# shield_sporecollector_v4.net
KiCad netlist of a schematic drawn in EAGLE
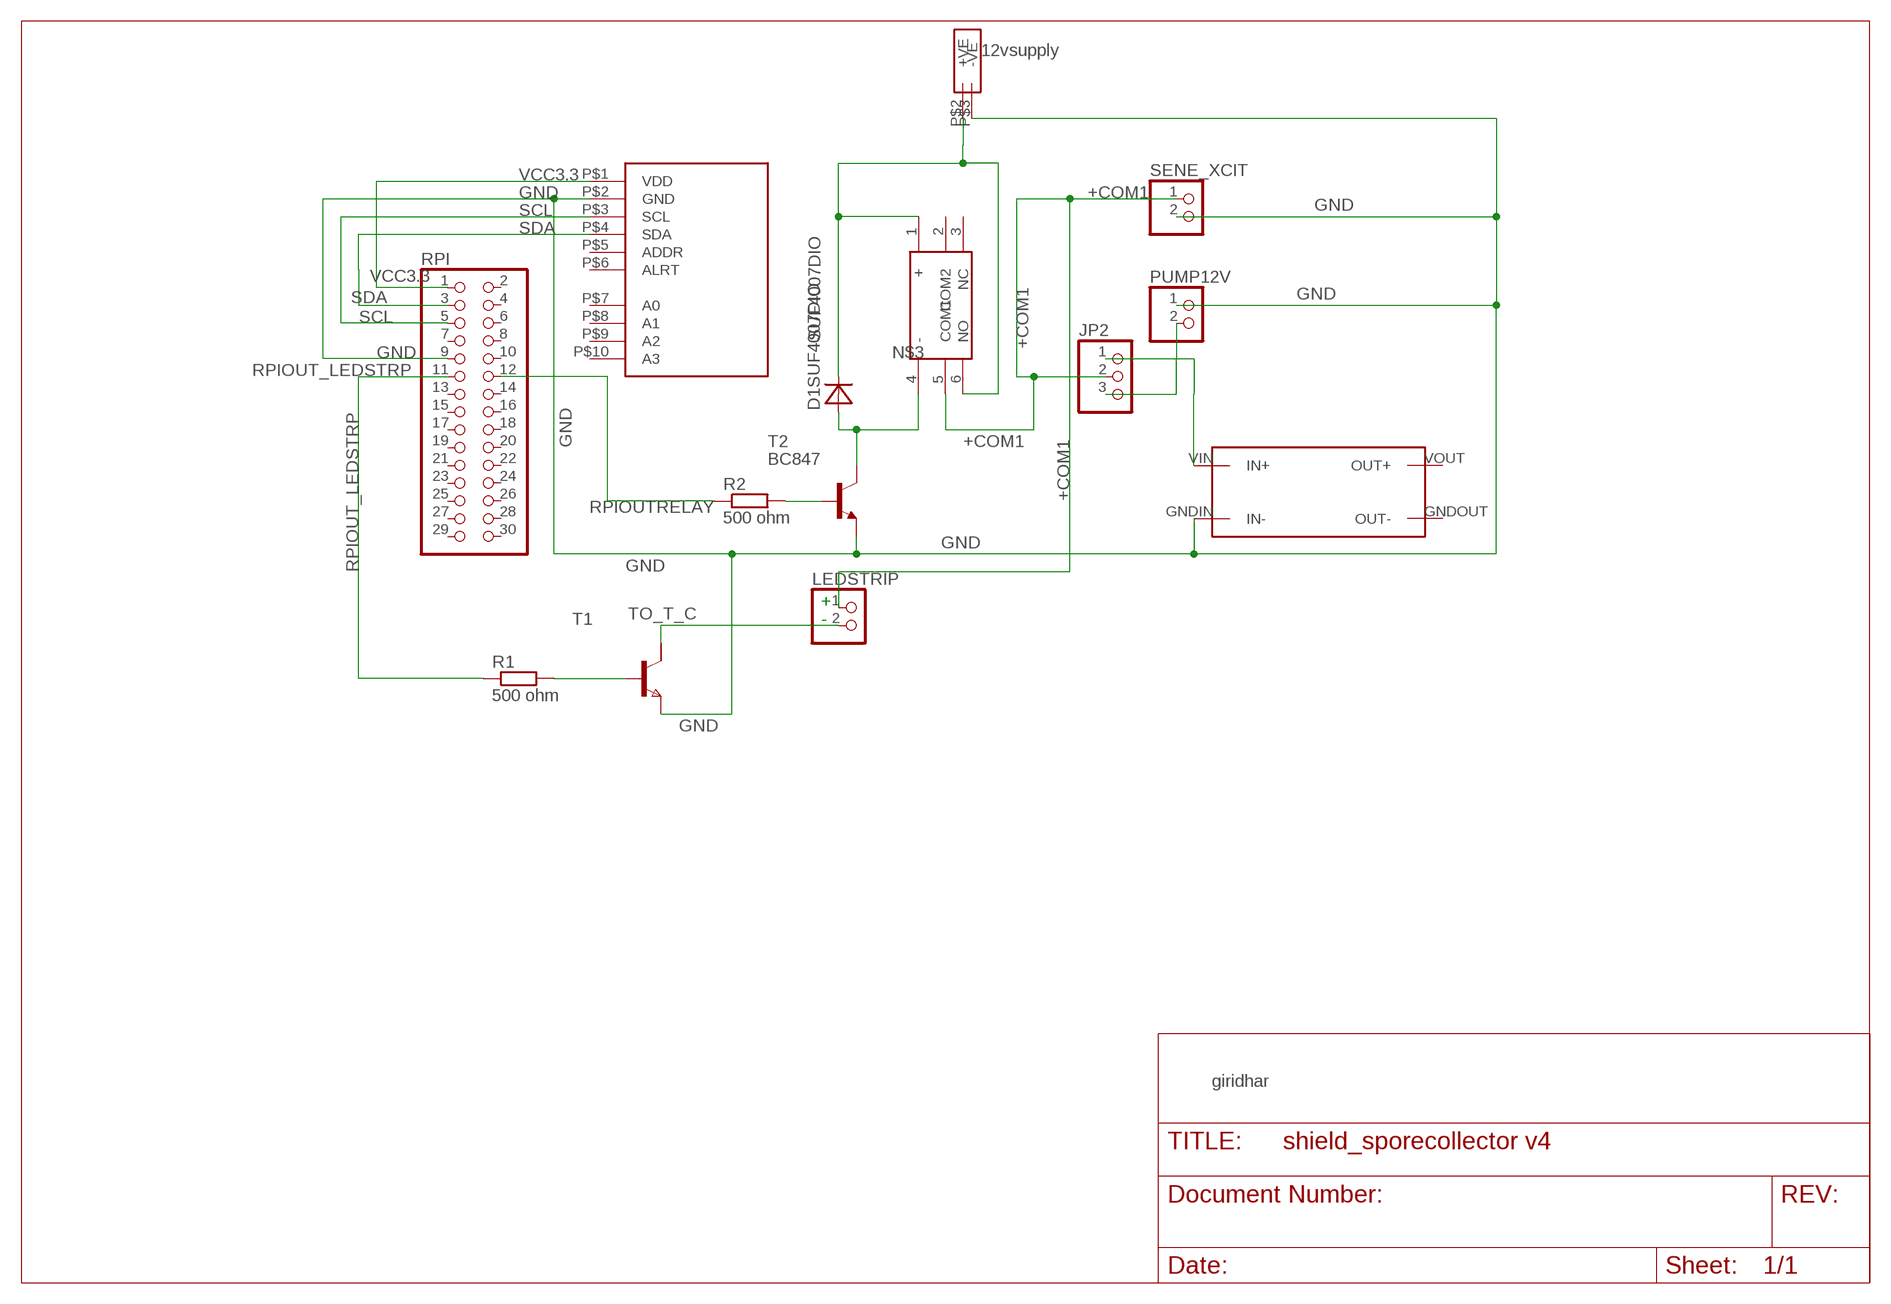
[diagram p0: schematic, sheet 1]

(export (version "E")
  (design (tool "Eeschema 10.0.6"))
  (components
    (comp (ref "BUCHSE12VINPUT")
      (value "BUCHSE9.8X14.6")
      (footprint "eagle-import:BUCHSE9.8X14.6")
      (libsource (lib "eagle-import") (part "BUCHSE9.8X14.6"))
    )
    (comp (ref "D1SUF4007DIO")
      (value "SUF4007DIO")
      (footprint "eagle-import:SUF4007")
      (libsource (lib "eagle-import") (part "SUF4007DIO"))
    )
    (comp (ref "JP2")
      (value "PINHD-1X3")
      (footprint "eagle-import:1X03")
      (libsource (lib "eagle-import") (part "PINHD-1X3"))
    )
    (comp (ref "LEDSTRIP")
      (value "PINHD-1X2")
      (footprint "eagle-import:1X02")
      (libsource (lib "eagle-import") (part "PINHD-1X2"))
    )
    (comp (ref "PUMP12V")
      (value "PINHD-1X2")
      (footprint "eagle-import:1X02")
      (libsource (lib "eagle-import") (part "PINHD-1X2"))
    )
    (comp (ref "R1")
      (value "500 ohm")
      (footprint "eagle-import:R0603")
      (libsource (lib "eagle-import") (part "R-EU_R0603"))
    )
    (comp (ref "R2")
      (value "500 ohm")
      (footprint "eagle-import:R0603")
      (libsource (lib "eagle-import") (part "R-EU_R0603"))
    )
    (comp (ref "RPI")
      (value "PINHD-2X15")
      (footprint "eagle-import:2X15")
      (libsource (lib "eagle-import") (part "PINHD-2X15"))
    )
    (comp (ref "SENE_XCIT")
      (value "PINHD-1X2")
      (footprint "eagle-import:1X02")
      (libsource (lib "eagle-import") (part "PINHD-1X2"))
    )
    (comp (ref "STEPUP12TO24V")
      (value "24VSTEPUPPOLOLUSMDSMD")
      (footprint "eagle-import:STEP-UP24VSMD")
      (libsource (lib "eagle-import") (part "24VSTEPUPPOLOLUSMDSMD"))
    )
    (comp (ref "T1")
      (value "NPNSOT223")
      (footprint "eagle-import:SOT223")
      (libsource (lib "eagle-import") (part "NPNSOT223"))
    )
    (comp (ref "T2")
      (value "BC847")
      (footprint "eagle-import:SOT23")
      (libsource (lib "eagle-import") (part "BC847"))
    )
    (comp (ref "U$3")
      (value "ADC-4CH-ADS1115/WITHOUTHOLESADC-ADS1115WITHOUTHOLES")
      (footprint "eagle-import:ADC-4CH-ADS1115_WITHOUTHOLES")
      (libsource (lib "eagle-import") (part "ADC-4CH-ADS1115/WITHOUTHOLESADC-ADS1115WITHOUTHOLES"))
    )
    (comp (ref "U$4")
      (value "G6B-2114POMRON")
      (footprint "eagle-import:G6B-2114P")
      (libsource (lib "eagle-import") (part "G6B-2114POMRON"))
    )
  )
  (nets
    (net (code "1") (name "/+COM1") (class "Default")
      (node (ref "JP2") (pin "2") (pinfunction "2_2") (pintype "passive"))
      (node (ref "LEDSTRIP") (pin "1") (pinfunction "1_1") (pintype "passive"))
      (node (ref "SENE_XCIT") (pin "1") (pinfunction "1_1") (pintype "passive"))
      (node (ref "U$4") (pin "5") (pinfunction "COM1_5") (pintype "bidirectional"))
    )
    (net (code "2") (name "/GND") (class "Default")
      (node (ref "BUCHSE12VINPUT") (pin "P$3") (pinfunction "-VE_P$3") (pintype "bidirectional"))
      (node (ref "PUMP12V") (pin "1") (pinfunction "1_1") (pintype "passive"))
      (node (ref "RPI") (pin "9") (pinfunction "9_9") (pintype "passive"))
      (node (ref "SENE_XCIT") (pin "2") (pinfunction "2_2") (pintype "passive"))
      (node (ref "STEPUP12TO24V") (pin "GNDIN") (pinfunction "IN-_GNDIN") (pintype "bidirectional"))
      (node (ref "T1") (pin "3") (pinfunction "E_3") (pintype "passive"))
      (node (ref "T2") (pin "2") (pinfunction "E_2") (pintype "passive"))
      (node (ref "U$3") (pin "P$2") (pinfunction "GND_P$2") (pintype "power_in"))
    )
    (net (code "3") (name "/N$3") (class "Default")
      (node (ref "BUCHSE12VINPUT") (pin "P$2") (pinfunction "+VE_P$2") (pintype "bidirectional"))
      (node (ref "D1SUF4007DIO") (pin "C") (pinfunction "C_C") (pintype "passive"))
      (node (ref "U$4") (pin "1") (pinfunction "+_1") (pintype "bidirectional"))
      (node (ref "U$4") (pin "6") (pinfunction "NO_6") (pintype "bidirectional"))
    )
    (net (code "4") (name "/RPIOUTRELAY") (class "Default")
      (node (ref "R2") (pin "1") (pinfunction "1_1") (pintype "passive"))
      (node (ref "RPI") (pin "12") (pinfunction "12_12") (pintype "passive"))
    )
    (net (code "5") (name "/RPIOUT_LEDSTRP") (class "Default")
      (node (ref "R1") (pin "1") (pinfunction "1_1") (pintype "passive"))
      (node (ref "RPI") (pin "11") (pinfunction "11_11") (pintype "passive"))
    )
    (net (code "6") (name "/SCL") (class "Default")
      (node (ref "RPI") (pin "5") (pinfunction "5_5") (pintype "passive"))
      (node (ref "U$3") (pin "P$3") (pinfunction "SCL_P$3") (pintype "bidirectional"))
    )
    (net (code "7") (name "/SDA") (class "Default")
      (node (ref "RPI") (pin "3") (pinfunction "3_3") (pintype "passive"))
      (node (ref "U$3") (pin "P$4") (pinfunction "SDA_P$4") (pintype "bidirectional"))
    )
    (net (code "8") (name "/TO_T_C") (class "Default")
      (node (ref "LEDSTRIP") (pin "2") (pinfunction "2_2") (pintype "passive"))
      (node (ref "T1") (pin "2") (pinfunction "C1_2") (pintype "passive"))
    )
    (net (code "9") (name "/VCC3.3") (class "Default")
      (node (ref "RPI") (pin "1") (pinfunction "1_1") (pintype "passive"))
      (node (ref "U$3") (pin "P$1") (pinfunction "VDD_P$1") (pintype "power_in"))
    )
    (net (code "10") (name "Net-(JP2-Pad3)") (class "Default")
      (node (ref "JP2") (pin "3") (pinfunction "3_3") (pintype "passive"))
      (node (ref "PUMP12V") (pin "2") (pinfunction "2_2") (pintype "passive"))
    )
    (net (code "11") (name "Net-(STEPUP12TO24V-IN+)") (class "Default")
      (node (ref "JP2") (pin "1") (pinfunction "1_1") (pintype "passive"))
      (node (ref "STEPUP12TO24V") (pin "VIN") (pinfunction "IN+_VIN") (pintype "bidirectional"))
    )
    (net (code "12") (name "Net-(T1-B)") (class "Default")
      (node (ref "R1") (pin "2") (pinfunction "2_2") (pintype "passive"))
      (node (ref "T1") (pin "1") (pinfunction "B_1") (pintype "passive"))
    )
    (net (code "13") (name "Net-(T2-B)") (class "Default")
      (node (ref "R2") (pin "2") (pinfunction "2_2") (pintype "passive"))
      (node (ref "T2") (pin "1") (pinfunction "B_1") (pintype "passive"))
    )
    (net (code "14") (name "Net-(T2-C)") (class "Default")
      (node (ref "D1SUF4007DIO") (pin "A") (pinfunction "A_A") (pintype "passive"))
      (node (ref "T2") (pin "3") (pinfunction "C_3") (pintype "passive"))
      (node (ref "U$4") (pin "4") (pinfunction "-_4") (pintype "bidirectional"))
    )
    (net (code "15") (name "unconnected-(RPI-Pad2)") (class "Default")
      (node (ref "RPI") (pin "2") (pinfunction "2_2") (pintype "passive"))
    )
    (net (code "16") (name "unconnected-(RPI-Pad4)") (class "Default")
      (node (ref "RPI") (pin "4") (pinfunction "4_4") (pintype "passive"))
    )
    (net (code "17") (name "unconnected-(RPI-Pad6)") (class "Default")
      (node (ref "RPI") (pin "6") (pinfunction "6_6") (pintype "passive"))
    )
    (net (code "18") (name "unconnected-(RPI-Pad7)") (class "Default")
      (node (ref "RPI") (pin "7") (pinfunction "7_7") (pintype "passive"))
    )
    (net (code "19") (name "unconnected-(RPI-Pad8)") (class "Default")
      (node (ref "RPI") (pin "8") (pinfunction "8_8") (pintype "passive"))
    )
    (net (code "20") (name "unconnected-(RPI-Pad10)") (class "Default")
      (node (ref "RPI") (pin "10") (pinfunction "10_10") (pintype "passive"))
    )
    (net (code "21") (name "unconnected-(RPI-Pad13)") (class "Default")
      (node (ref "RPI") (pin "13") (pinfunction "13_13") (pintype "passive"))
    )
    (net (code "22") (name "unconnected-(RPI-Pad14)") (class "Default")
      (node (ref "RPI") (pin "14") (pinfunction "14_14") (pintype "passive"))
    )
    (net (code "23") (name "unconnected-(RPI-Pad15)") (class "Default")
      (node (ref "RPI") (pin "15") (pinfunction "15_15") (pintype "passive"))
    )
    (net (code "24") (name "unconnected-(RPI-Pad16)") (class "Default")
      (node (ref "RPI") (pin "16") (pinfunction "16_16") (pintype "passive"))
    )
    (net (code "25") (name "unconnected-(RPI-Pad17)") (class "Default")
      (node (ref "RPI") (pin "17") (pinfunction "17_17") (pintype "passive"))
    )
    (net (code "26") (name "unconnected-(RPI-Pad18)") (class "Default")
      (node (ref "RPI") (pin "18") (pinfunction "18_18") (pintype "passive"))
    )
    (net (code "27") (name "unconnected-(RPI-Pad19)") (class "Default")
      (node (ref "RPI") (pin "19") (pinfunction "19_19") (pintype "passive"))
    )
    (net (code "28") (name "unconnected-(RPI-Pad20)") (class "Default")
      (node (ref "RPI") (pin "20") (pinfunction "20_20") (pintype "passive"))
    )
    (net (code "29") (name "unconnected-(RPI-Pad21)") (class "Default")
      (node (ref "RPI") (pin "21") (pinfunction "21_21") (pintype "passive"))
    )
    (net (code "30") (name "unconnected-(RPI-Pad22)") (class "Default")
      (node (ref "RPI") (pin "22") (pinfunction "22_22") (pintype "passive"))
    )
    (net (code "31") (name "unconnected-(RPI-Pad23)") (class "Default")
      (node (ref "RPI") (pin "23") (pinfunction "23_23") (pintype "passive"))
    )
    (net (code "32") (name "unconnected-(RPI-Pad24)") (class "Default")
      (node (ref "RPI") (pin "24") (pinfunction "24_24") (pintype "passive"))
    )
    (net (code "33") (name "unconnected-(RPI-Pad25)") (class "Default")
      (node (ref "RPI") (pin "25") (pinfunction "25_25") (pintype "passive"))
    )
    (net (code "34") (name "unconnected-(RPI-Pad26)") (class "Default")
      (node (ref "RPI") (pin "26") (pinfunction "26_26") (pintype "passive"))
    )
    (net (code "35") (name "unconnected-(RPI-Pad27)") (class "Default")
      (node (ref "RPI") (pin "27") (pinfunction "27_27") (pintype "passive"))
    )
    (net (code "36") (name "unconnected-(RPI-Pad28)") (class "Default")
      (node (ref "RPI") (pin "28") (pinfunction "28_28") (pintype "passive"))
    )
    (net (code "37") (name "unconnected-(RPI-Pad29)") (class "Default")
      (node (ref "RPI") (pin "29") (pinfunction "29_29") (pintype "passive"))
    )
    (net (code "38") (name "unconnected-(RPI-Pad30)") (class "Default")
      (node (ref "RPI") (pin "30") (pinfunction "30_30") (pintype "passive"))
    )
    (net (code "39") (name "unconnected-(STEPUP12TO24V-OUT+-PadVOUT)") (class "Default")
      (node (ref "STEPUP12TO24V") (pin "VOUT") (pinfunction "OUT+_VOUT") (pintype "bidirectional"))
    )
    (net (code "40") (name "unconnected-(STEPUP12TO24V-OUT--PadGNDOUT)") (class "Default")
      (node (ref "STEPUP12TO24V") (pin "GNDOUT") (pinfunction "OUT-_GNDOUT") (pintype "bidirectional"))
    )
    (net (code "41") (name "unconnected-(T1-C2-Pad4)") (class "Default")
      (node (ref "T1") (pin "4") (pinfunction "C2_4") (pintype "passive"))
    )
    (net (code "42") (name "unconnected-(U$3-A0-PadP$7)") (class "Default")
      (node (ref "U$3") (pin "P$7") (pinfunction "A0_P$7") (pintype "input"))
    )
    (net (code "43") (name "unconnected-(U$3-A1-PadP$8)") (class "Default")
      (node (ref "U$3") (pin "P$8") (pinfunction "A1_P$8") (pintype "input"))
    )
    (net (code "44") (name "unconnected-(U$3-A2-PadP$9)") (class "Default")
      (node (ref "U$3") (pin "P$9") (pinfunction "A2_P$9") (pintype "input"))
    )
    (net (code "45") (name "unconnected-(U$3-A3-PadP$10)") (class "Default")
      (node (ref "U$3") (pin "P$10") (pinfunction "A3_P$10") (pintype "input"))
    )
    (net (code "46") (name "unconnected-(U$3-ADDR-PadP$5)") (class "Default")
      (node (ref "U$3") (pin "P$5") (pinfunction "ADDR_P$5") (pintype "bidirectional"))
    )
    (net (code "47") (name "unconnected-(U$3-ALRT-PadP$6)") (class "Default")
      (node (ref "U$3") (pin "P$6") (pinfunction "ALRT_P$6") (pintype "bidirectional"))
    )
    (net (code "48") (name "unconnected-(U$4-COM2-Pad2)") (class "Default")
      (node (ref "U$4") (pin "2") (pinfunction "COM2_2") (pintype "bidirectional"))
    )
    (net (code "49") (name "unconnected-(U$4-NC-Pad3)") (class "Default")
      (node (ref "U$4") (pin "3") (pinfunction "NC_3") (pintype "bidirectional"))
    )
  )
)
